# SPD.net
KiCad netlist of a schematic drawn in Altium Designer
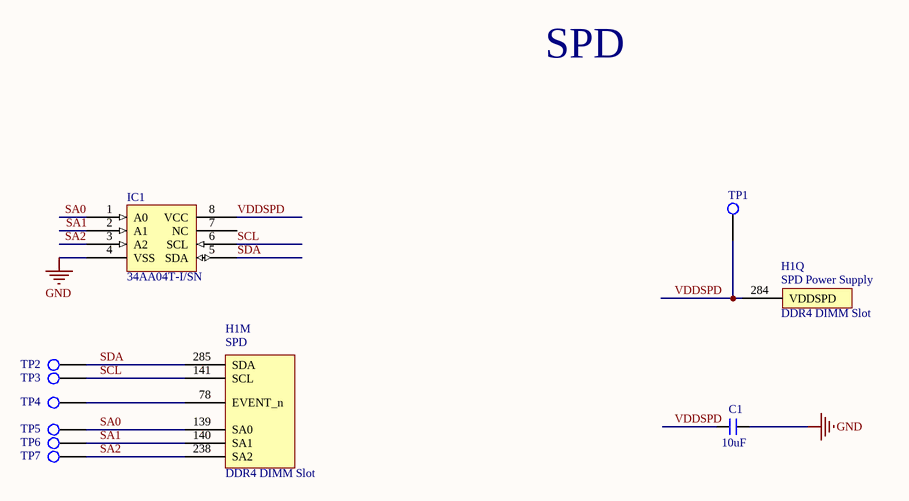
[diagram p0: SPD.SchDoc]

(export (version "E")
  (design (tool "Eeschema 10.0.6"))
  (components
    (comp (ref "C1")
      (value "Capacitor 0603")
      (footprint "Capacitor 0603")
      (fields
        (field (name "MANUFACTURER") "Vishay")
        (field (name "MANUFACTURER PART NUMBER") "CRCW060310K0FKEA")
        (field (name "TOLERANCE") "1%")
        (field (name "CAPACITANCE") "10uF")
      )
      (libsource (lib "RouterIntLib") (part "Capacitor 0603"))
    )
    (comp (ref "H1")
      (value "DDR4 DIMM Slot")
      (footprint "DDR4 DIMM")
      (libsource (lib "RouterIntLib") (part "DDR4 DIMM Slot"))
    )
    (comp (ref "IC1")
      (value "34AA04T-I/SN")
      (footprint "34AA04T-I/SN")
      (libsource (lib "RouterIntLib") (part "34AA04T-I/SN"))
    )
    (comp (ref "TP1")
      (value "Test Point")
      (footprint "Test Point")
      (libsource (lib "RouterIntLib") (part "Test Point"))
    )
    (comp (ref "TP2")
      (value "Test Point")
      (footprint "Test Point")
      (libsource (lib "RouterIntLib") (part "Test Point"))
    )
    (comp (ref "TP3")
      (value "Test Point")
      (footprint "Test Point")
      (libsource (lib "RouterIntLib") (part "Test Point"))
    )
    (comp (ref "TP4")
      (value "Test Point")
      (footprint "Test Point")
      (libsource (lib "RouterIntLib") (part "Test Point"))
    )
    (comp (ref "TP5")
      (value "Test Point")
      (footprint "Test Point")
      (libsource (lib "RouterIntLib") (part "Test Point"))
    )
    (comp (ref "TP6")
      (value "Test Point")
      (footprint "Test Point")
      (libsource (lib "RouterIntLib") (part "Test Point"))
    )
    (comp (ref "TP7")
      (value "Test Point")
      (footprint "Test Point")
      (libsource (lib "RouterIntLib") (part "Test Point"))
    )
  )
  (nets
    (net (code "1") (name "/SA0") (class "Default")
      (node (ref "H1") (pin "139") (pinfunction "SA0_139") (pintype "passive"))
      (node (ref "IC1") (pin "1") (pinfunction "A0_1") (pintype "input"))
      (node (ref "TP5") (pin "1") (pinfunction "1_1") (pintype "passive"))
    )
    (net (code "2") (name "/SA1") (class "Default")
      (node (ref "H1") (pin "140") (pinfunction "SA1_140") (pintype "passive"))
      (node (ref "IC1") (pin "2") (pinfunction "A1_2") (pintype "input"))
      (node (ref "TP6") (pin "1") (pinfunction "1_1") (pintype "passive"))
    )
    (net (code "3") (name "/SA2") (class "Default")
      (node (ref "H1") (pin "238") (pinfunction "SA2_238") (pintype "passive"))
      (node (ref "IC1") (pin "3") (pinfunction "A2_3") (pintype "input"))
      (node (ref "TP7") (pin "1") (pinfunction "1_1") (pintype "passive"))
    )
    (net (code "4") (name "/SCL") (class "Default")
      (node (ref "H1") (pin "141") (pinfunction "SCL_141") (pintype "passive"))
      (node (ref "IC1") (pin "6") (pinfunction "SCL_6") (pintype "input"))
      (node (ref "TP3") (pin "1") (pinfunction "1_1") (pintype "passive"))
    )
    (net (code "5") (name "/SDA") (class "Default")
      (node (ref "H1") (pin "285") (pinfunction "SDA_285") (pintype "passive"))
      (node (ref "IC1") (pin "5") (pinfunction "SDA_5") (pintype "bidirectional"))
      (node (ref "TP2") (pin "1") (pinfunction "1_1") (pintype "passive"))
    )
    (net (code "6") (name "/VDDSPD") (class "Default")
      (node (ref "C1") (pin "1") (pinfunction "1_1") (pintype "passive"))
      (node (ref "H1") (pin "284") (pinfunction "VDDSPD_284") (pintype "passive"))
      (node (ref "IC1") (pin "8") (pinfunction "VCC_8") (pintype "power_in"))
      (node (ref "TP1") (pin "1") (pinfunction "1_1") (pintype "passive"))
    )
    (net (code "7") (name "GND") (class "Default")
      (node (ref "C1") (pin "2") (pinfunction "2_2") (pintype "passive"))
      (node (ref "IC1") (pin "4") (pinfunction "VSS_4") (pintype "passive"))
    )
    (net (code "8") (name "Net-(H1M-EVENT_n)") (class "Default")
      (node (ref "H1") (pin "78") (pinfunction "EVENT_n_78") (pintype "passive"))
      (node (ref "TP4") (pin "1") (pinfunction "1_1") (pintype "passive"))
    )
    (net (code "9") (name "unconnected-(IC1-NC-Pad7)") (class "Default")
      (node (ref "IC1") (pin "7") (pinfunction "NC_7") (pintype "passive"))
    )
  )
)
